# 09_MT7688AN_Peripheral.net
KiCad netlist of a schematic drawn in Altium Designer
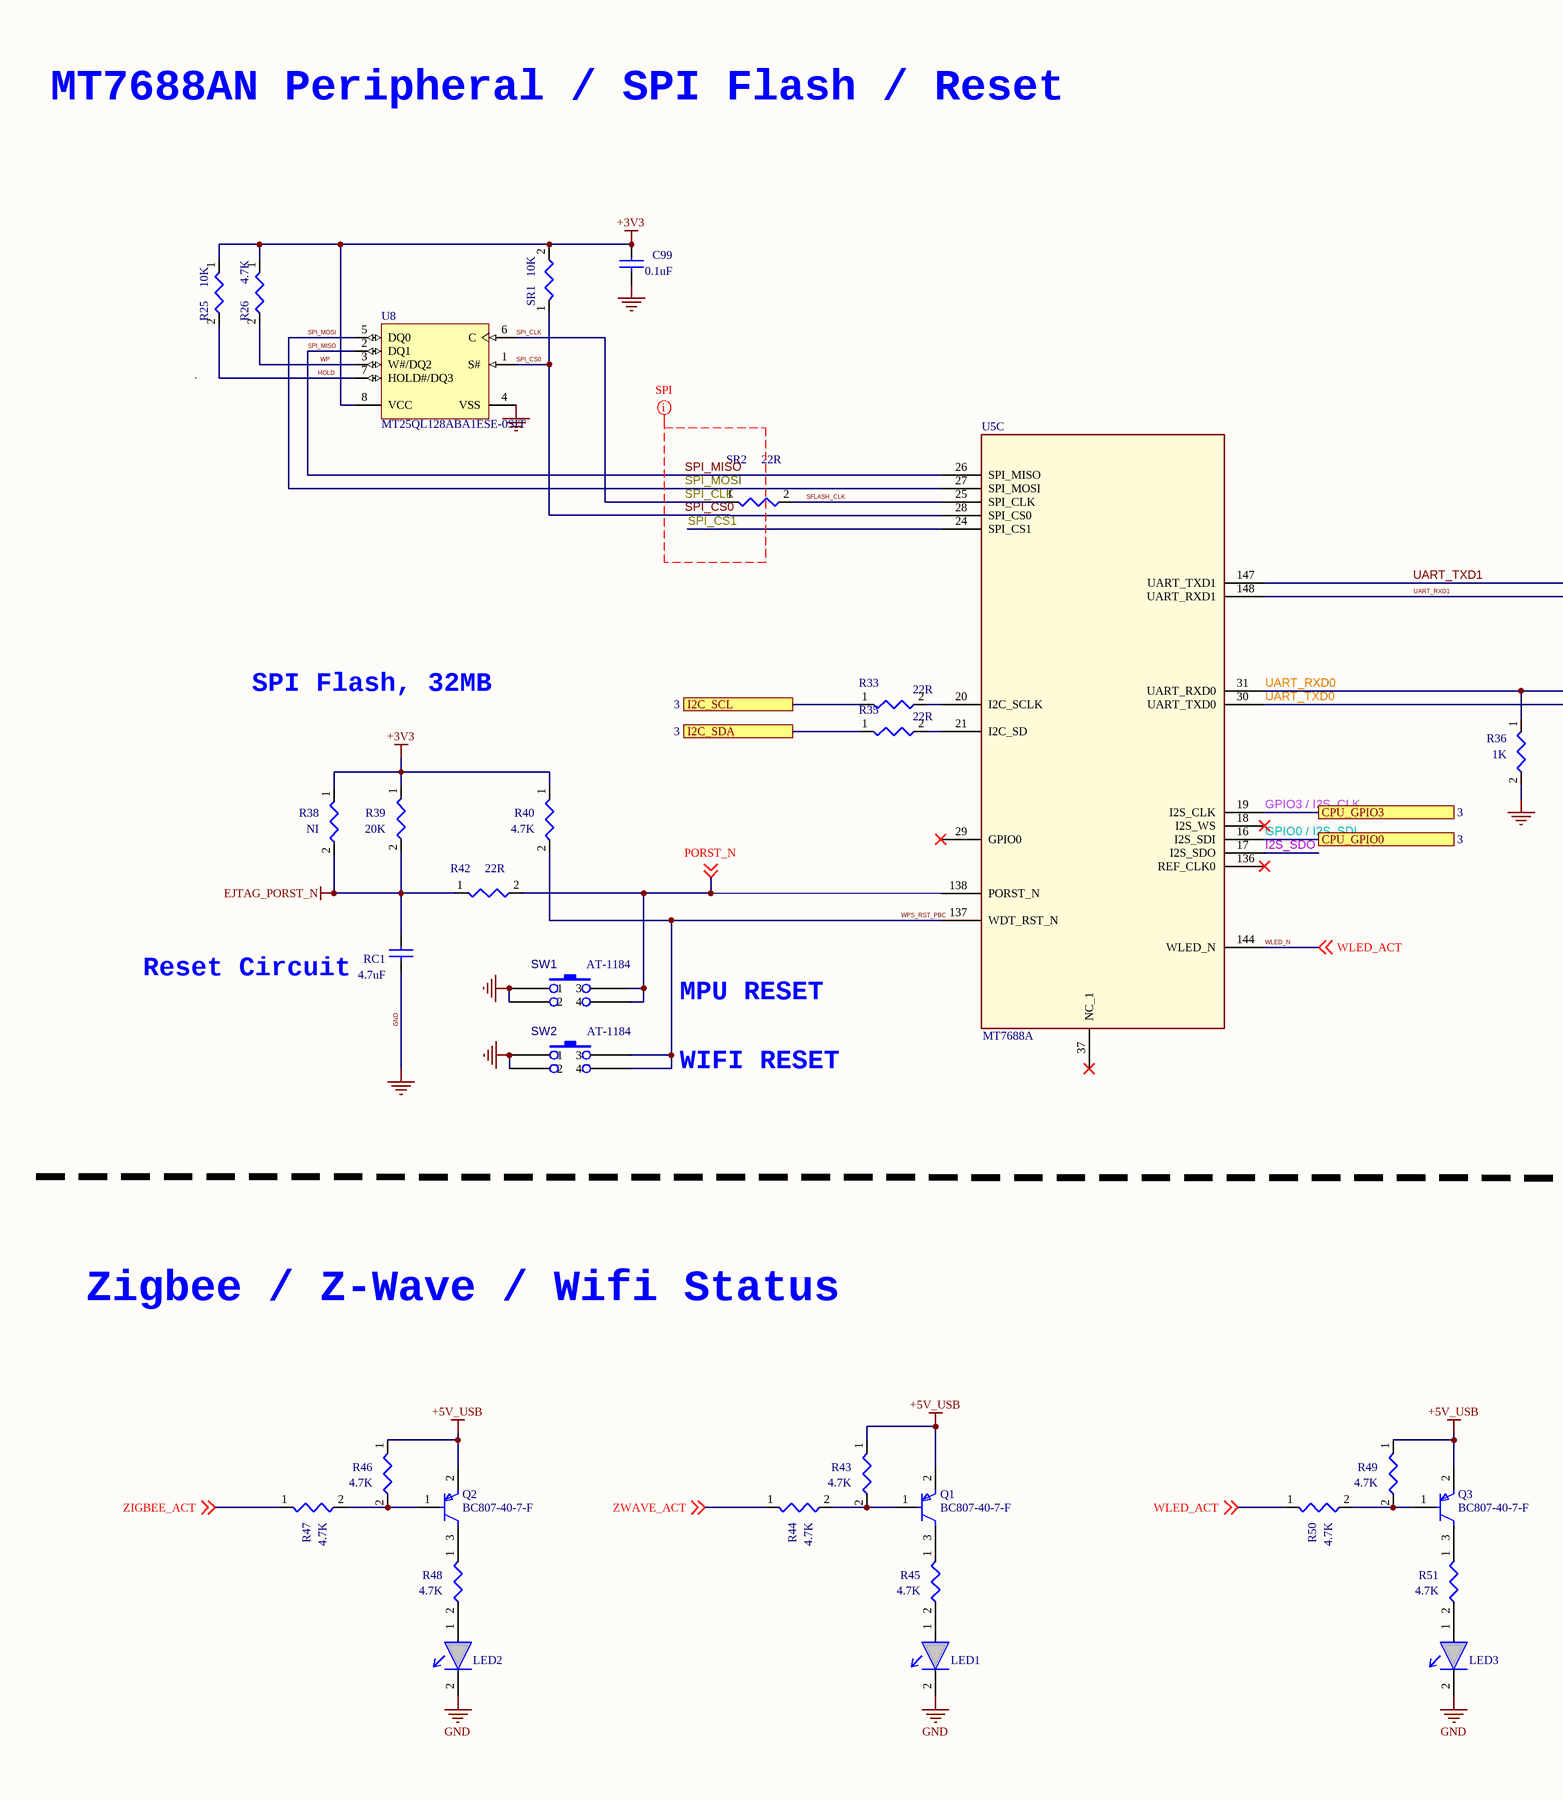
[diagram p0: 09. MT7688AN Peripheral.SchDoc, left]
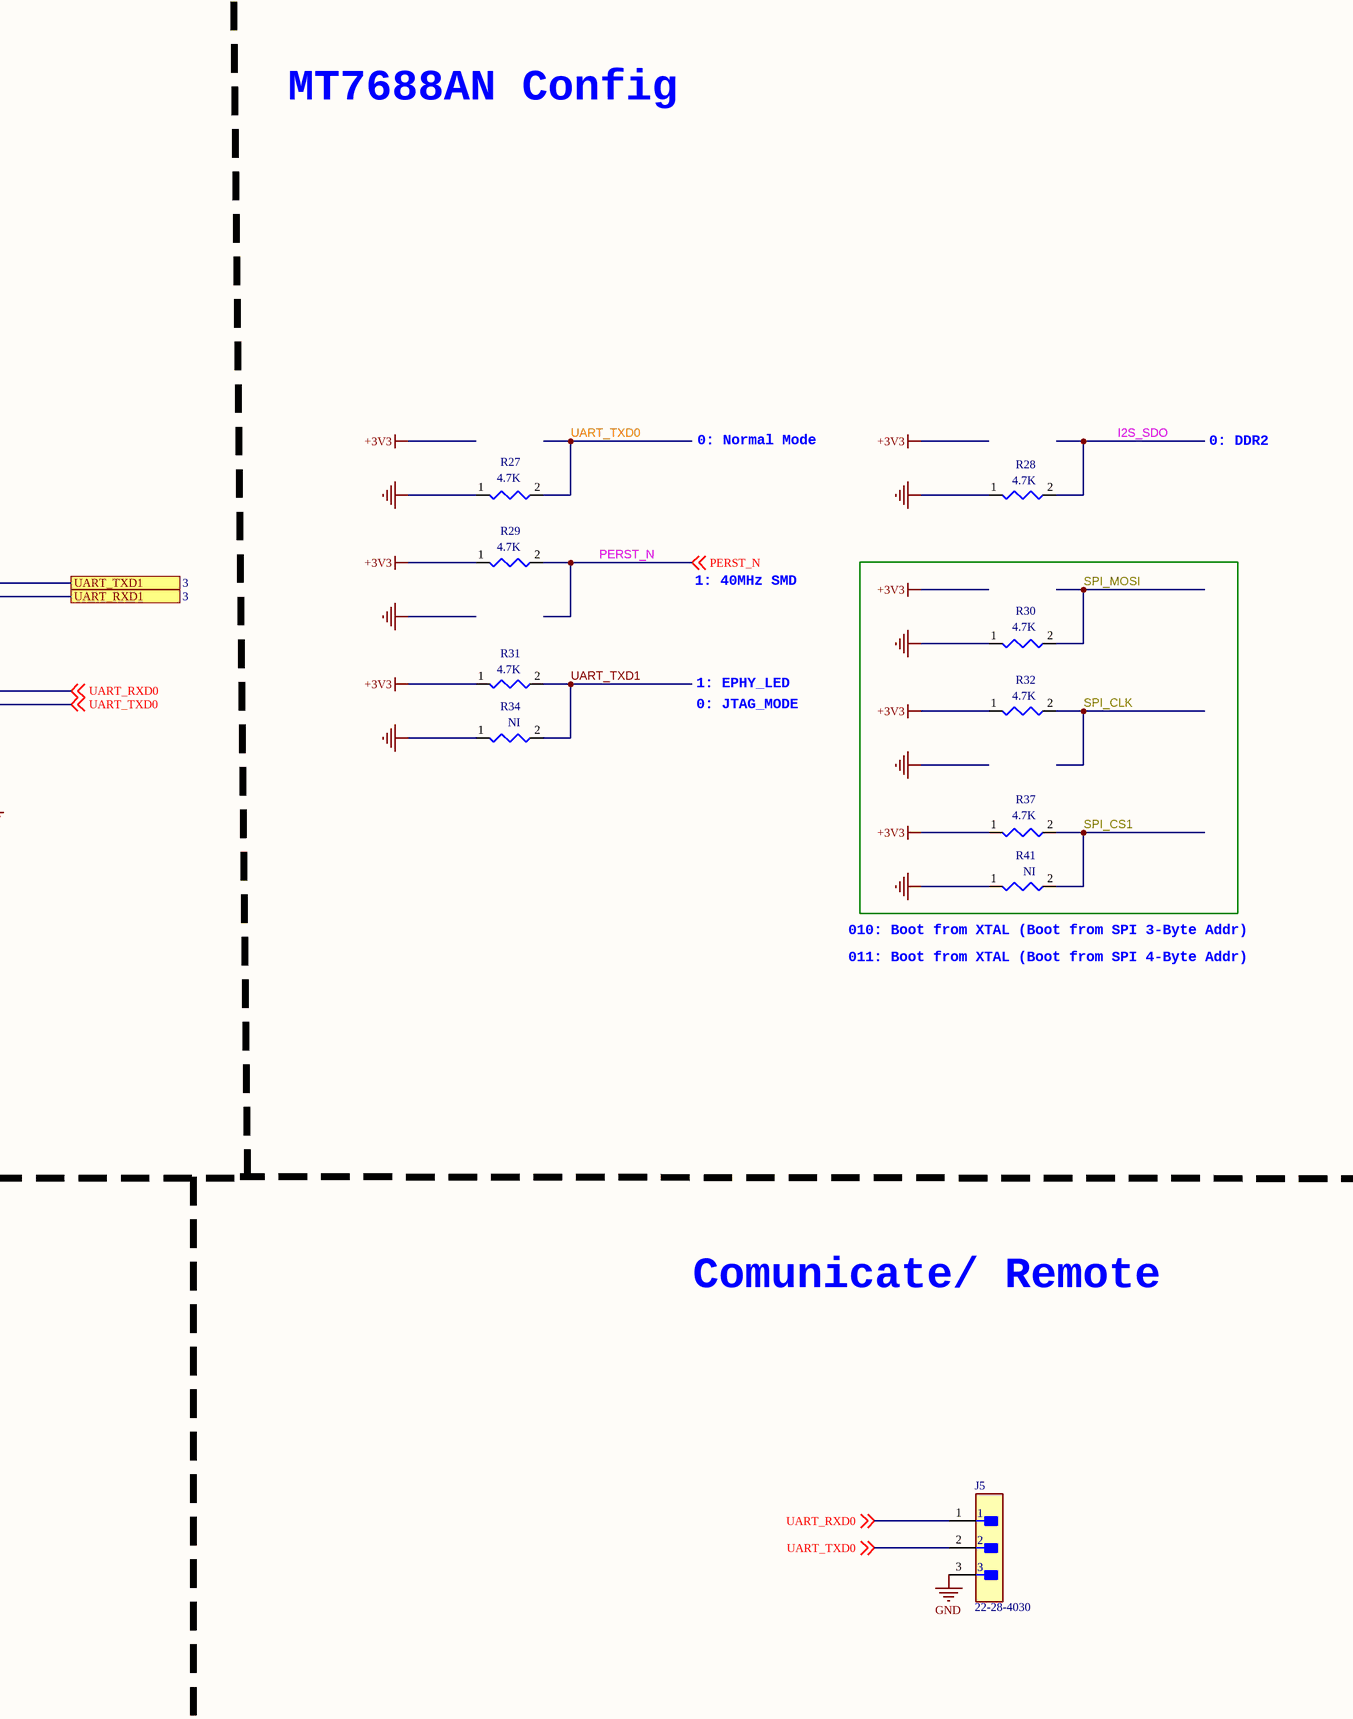
[diagram p1: 09. MT7688AN Peripheral.SchDoc, right]

(export (version "E")
  (design (tool "Eeschema 10.0.6"))
  (components
    (comp (ref "C99")
      (value "0.1uF")
      (footprint "CAPC1005X60X30NL05T10")
      (libsource (lib "MT7688AN") (part "CAP NP"))
    )
    (comp (ref "J5")
      (value "22-28-4030")
      (footprint "FP-22-28-4030-MFG")
      (description "CONN HEADER VERT 3POS 2.54MM")
      (fields
        (field (name "OCTOPART") "https://octopart.com/0022284030-molex-10476094")
        (field (name "MANUFACTURER") "Molex")
      )
      (libsource (lib "Altium Content Vault") (part "0d3f023dd272f625e17a2be33dea85f"))
    )
    (comp (ref "LED1")
      (value "LED 2P")
      (footprint "LED3MM 2P")
      (libsource (lib "SyTungNguyen") (part "LED 2P"))
    )
    (comp (ref "LED2")
      (value "LED 2P")
      (footprint "LED3MM 2P")
      (libsource (lib "SyTungNguyen") (part "LED 2P"))
    )
    (comp (ref "LED3")
      (value "LED 2P")
      (footprint "LED3MM 2P")
      (libsource (lib "SyTungNguyen") (part "LED 2P"))
    )
    (comp (ref "Q1")
      (value "BC807-40-7-F")
      (footprint "FP-SOT23-MFG")
      (description "TRANS PNP 45V 0.5A SOT23")
      (fields
        (field (name "OCTOPART") "https://octopart.com/bc807-40-7-f-diodes+inc.-354302")
        (field (name "MANUFACTURER") "DIODES INC.")
      )
      (libsource (lib "Altium Content Vault") (part "0e8486ed3b47d9c69b8404ba87cf0f7"))
    )
    (comp (ref "Q2")
      (value "BC807-40-7-F")
      (footprint "FP-SOT23-MFG")
      (description "TRANS PNP 45V 0.5A SOT23")
      (fields
        (field (name "OCTOPART") "https://octopart.com/bc807-40-7-f-diodes+inc.-354302")
        (field (name "MANUFACTURER") "DIODES INC.")
      )
      (libsource (lib "Altium Content Vault") (part "0e8486ed3b47d9c69b8404ba87cf0f7"))
    )
    (comp (ref "Q3")
      (value "BC807-40-7-F")
      (footprint "FP-SOT23-MFG")
      (description "TRANS PNP 45V 0.5A SOT23")
      (fields
        (field (name "OCTOPART") "https://octopart.com/bc807-40-7-f-diodes+inc.-354302")
        (field (name "MANUFACTURER") "DIODES INC.")
      )
      (libsource (lib "Altium Content Vault") (part "0e8486ed3b47d9c69b8404ba87cf0f7"))
    )
    (comp (ref "R25")
      (value "10K")
      (footprint "RESC1005X35X25NL10T10")
      (libsource (lib "MT7688AN") (part "RES/0402_3"))
    )
    (comp (ref "R26")
      (value "4.7K")
      (footprint "RESC1005X35X25NL10T10")
      (libsource (lib "MT7688AN") (part "RES/0402_3"))
    )
    (comp (ref "R27")
      (value "4.7K")
      (footprint "RESC1005X35X25NL10T10")
      (libsource (lib "MT7688AN") (part "RES/0402_3"))
    )
    (comp (ref "R28")
      (value "4.7K")
      (footprint "RESC1005X35X25NL10T10")
      (libsource (lib "MT7688AN") (part "RES/0402_3"))
    )
    (comp (ref "R29")
      (value "4.7K")
      (footprint "RESC1005X35X25NL10T10")
      (libsource (lib "MT7688AN") (part "RES/0402_3"))
    )
    (comp (ref "R30")
      (value "4.7K")
      (footprint "RESC1005X35X25NL10T10")
      (libsource (lib "MT7688AN") (part "RES/0402_3"))
    )
    (comp (ref "R31")
      (value "4.7K")
      (footprint "RESC1005X35X25NL10T10")
      (libsource (lib "MT7688AN") (part "RES/0402_3"))
    )
    (comp (ref "R32")
      (value "4.7K")
      (footprint "RESC1005X35X25NL10T10")
      (libsource (lib "MT7688AN") (part "RES/0402_3"))
    )
    (comp (ref "R33")
      (value "22R")
      (footprint "RESC1005X35X25NL10T10")
      (libsource (lib "MT7688AN") (part "RES/0402_3"))
    )
    (comp (ref "R34")
      (value "NI")
      (footprint "RESC1005X35X25NL10T10")
      (libsource (lib "MT7688AN") (part "RES/0402_3"))
    )
    (comp (ref "R35")
      (value "22R")
      (footprint "RESC1005X35X25NL10T10")
      (libsource (lib "MT7688AN") (part "RES/0402_3"))
    )
    (comp (ref "R36")
      (value "1K")
      (footprint "RESC1005X35X25NL10T10")
      (libsource (lib "MT7688AN") (part "RES/0402_3"))
    )
    (comp (ref "R37")
      (value "4.7K")
      (footprint "RESC1005X35X25NL10T10")
      (libsource (lib "MT7688AN") (part "RES/0402_3"))
    )
    (comp (ref "R38")
      (value "NI")
      (footprint "RESC1005X35X25NL10T10")
      (libsource (lib "MT7688AN") (part "RES/0402_3"))
    )
    (comp (ref "R39")
      (value "20K")
      (footprint "RESC1005X35X25NL10T10")
      (libsource (lib "MT7688AN") (part "RES/0402_3"))
    )
    (comp (ref "R40")
      (value "4.7K")
      (footprint "RESC1005X35X25NL10T10")
      (libsource (lib "MT7688AN") (part "RES/0402_3"))
    )
    (comp (ref "R41")
      (value "NI")
      (footprint "RESC1005X35X25NL10T10")
      (libsource (lib "MT7688AN") (part "RES/0402_3"))
    )
    (comp (ref "R42")
      (value "22R")
      (footprint "RESC1005X35X25NL10T10")
      (libsource (lib "MT7688AN") (part "RES/0402_3"))
    )
    (comp (ref "R43")
      (value "4.7K")
      (footprint "RESC1005X35X25NL10T10")
      (libsource (lib "MT7688AN") (part "RES/0402_3"))
    )
    (comp (ref "R44")
      (value "4.7K")
      (footprint "RESC1005X35X25NL10T10")
      (libsource (lib "MT7688AN") (part "RES/0402_3"))
    )
    (comp (ref "R45")
      (value "4.7K")
      (footprint "RESC1609X50X30NL10T20")
      (libsource (lib "MT7688AN") (part "RES/0402_3"))
    )
    (comp (ref "R46")
      (value "4.7K")
      (footprint "RESC1005X35X25NL10T10")
      (libsource (lib "MT7688AN") (part "RES/0402_3"))
    )
    (comp (ref "R47")
      (value "4.7K")
      (footprint "RESC1005X35X25NL10T10")
      (libsource (lib "MT7688AN") (part "RES/0402_3"))
    )
    (comp (ref "R48")
      (value "4.7K")
      (footprint "RESC1609X50X30NL10T20")
      (libsource (lib "MT7688AN") (part "RES/0402_3"))
    )
    (comp (ref "R49")
      (value "4.7K")
      (footprint "RESC1005X35X25NL10T10")
      (libsource (lib "MT7688AN") (part "RES/0402_3"))
    )
    (comp (ref "R50")
      (value "4.7K")
      (footprint "RESC1005X35X25NL10T10")
      (libsource (lib "MT7688AN") (part "RES/0402_3"))
    )
    (comp (ref "R51")
      (value "4.7K")
      (footprint "RESC1609X50X30NL10T20")
      (libsource (lib "MT7688AN") (part "RES/0402_3"))
    )
    (comp (ref "RC1")
      (value "4.7uF")
      (footprint "CAPC1005X60X30NL05T10")
      (libsource (lib "MT7688AN") (part "CAP NP"))
    )
    (comp (ref "SR1")
      (value "10K")
      (footprint "RESC1005X35X25NL10T10")
      (libsource (lib "MT7688AN") (part "RES/0402_3"))
    )
    (comp (ref "SR2")
      (value "22R")
      (footprint "RESC1005X35X25NL10T10")
      (libsource (lib "MT7688AN") (part "RES/0402_3"))
    )
    (comp (ref "SW1")
      (value "AT-1184")
      (footprint "AT-1184 SW")
      (description "TACT Switch, H=1.5mm")
      (fields (field (name "MANUFACTURER") "Panasonic - ECG"))
      (libsource (lib "MT7688AN") (part "SW"))
    )
    (comp (ref "SW2")
      (value "AT-1184")
      (footprint "AT-1184 SW")
      (description "TACT Switch, H=1.5mm")
      (fields (field (name "MANUFACTURER") "Panasonic - ECG"))
      (libsource (lib "MT7688AN") (part "SW"))
    )
    (comp (ref "U5")
      (value "MT7688A")
      (footprint "MT7628AN$2F$DRQFN156$2F$SMD$2F$P0.5$2F$12X12")
      (libsource (lib "MT7688AN") (part "MT7620N-n_26"))
    )
    (comp (ref "U8")
      (value "MT25QL128ABA1ESE-0SIT")
      (footprint "SOIC8_N")
      (fields (field (name "MANUFACTURER") "Micron"))
      (libsource (lib "HAGateWay202205V10") (part "MICT-MT25QL128ABA-SOP2-8"))
    )
  )
  (nets
    (net (code "1") (name "+3V3") (class "Default")
      (node (ref "C99") (pin "1") (pinfunction "1_1") (pintype "passive"))
      (node (ref "R25") (pin "1") (pinfunction "1_1") (pintype "passive"))
      (node (ref "R26") (pin "1") (pinfunction "1_1") (pintype "passive"))
      (node (ref "R29") (pin "1") (pinfunction "1_1") (pintype "passive"))
      (node (ref "R31") (pin "1") (pinfunction "1_1") (pintype "passive"))
      (node (ref "R32") (pin "1") (pinfunction "1_1") (pintype "passive"))
      (node (ref "R37") (pin "1") (pinfunction "1_1") (pintype "passive"))
      (node (ref "R38") (pin "1") (pinfunction "1_1") (pintype "passive"))
      (node (ref "R39") (pin "1") (pinfunction "1_1") (pintype "passive"))
      (node (ref "R40") (pin "1") (pinfunction "1_1") (pintype "passive"))
      (node (ref "SR1") (pin "2") (pinfunction "2_2") (pintype "passive"))
      (node (ref "U8") (pin "8") (pinfunction "VCC_8") (pintype "power_in"))
    )
    (net (code "2") (name "+5V_USB") (class "Default")
      (node (ref "Q1") (pin "2") (pinfunction "E_2") (pintype "passive"))
      (node (ref "Q2") (pin "2") (pinfunction "E_2") (pintype "passive"))
      (node (ref "Q3") (pin "2") (pinfunction "E_2") (pintype "passive"))
      (node (ref "R43") (pin "1") (pinfunction "1_1") (pintype "passive"))
      (node (ref "R46") (pin "1") (pinfunction "1_1") (pintype "passive"))
      (node (ref "R49") (pin "1") (pinfunction "1_1") (pintype "passive"))
    )
    (net (code "3") (name "/GPIO0 {slash} I2S_SDI") (class "Default")
      (node (ref "U5") (pin "16") (pinfunction "I2S_SDI_16") (pintype "passive"))
    )
    (net (code "4") (name "/GPIO3 {slash} I2S_CLK") (class "Default")
      (node (ref "U5") (pin "19") (pinfunction "I2S_CLK_19") (pintype "passive"))
    )
    (net (code "5") (name "/HOLD") (class "Default")
      (node (ref "R25") (pin "2") (pinfunction "2_2") (pintype "passive"))
      (node (ref "U8") (pin "7") (pinfunction "HOLD#/DQ3_7") (pintype "bidirectional"))
    )
    (net (code "6") (name "/I2C_SCL") (class "Default")
      (node (ref "R33") (pin "1") (pinfunction "1_1") (pintype "passive"))
    )
    (net (code "7") (name "/I2C_SDA") (class "Default")
      (node (ref "R35") (pin "1") (pinfunction "1_1") (pintype "passive"))
    )
    (net (code "8") (name "/I2S_SDO") (class "Default")
      (node (ref "R28") (pin "2") (pinfunction "2_2") (pintype "passive"))
      (node (ref "U5") (pin "17") (pinfunction "I2S_SDO_17") (pintype "passive"))
    )
    (net (code "9") (name "/SFLASH_CLK") (class "Default")
      (node (ref "SR2") (pin "2") (pinfunction "2_2") (pintype "passive"))
      (node (ref "U5") (pin "25") (pinfunction "SPI_CLK_25") (pintype "passive"))
    )
    (net (code "10") (name "/SPI_CLK") (class "Default")
      (node (ref "R32") (pin "2") (pinfunction "2_2") (pintype "passive"))
      (node (ref "SR2") (pin "1") (pinfunction "1_1") (pintype "passive"))
      (node (ref "U8") (pin "6") (pinfunction "C_6") (pintype "input"))
    )
    (net (code "11") (name "/SPI_CS0") (class "Default")
      (node (ref "SR1") (pin "1") (pinfunction "1_1") (pintype "passive"))
      (node (ref "U5") (pin "28") (pinfunction "SPI_CS0_28") (pintype "passive"))
      (node (ref "U8") (pin "1") (pinfunction "S#_1") (pintype "input"))
    )
    (net (code "12") (name "/SPI_CS1") (class "Default")
      (node (ref "R37") (pin "2") (pinfunction "2_2") (pintype "passive"))
      (node (ref "R41") (pin "2") (pinfunction "2_2") (pintype "passive"))
      (node (ref "U5") (pin "24") (pinfunction "SPI_CS1_24") (pintype "passive"))
    )
    (net (code "13") (name "/SPI_MISO") (class "Default")
      (node (ref "U5") (pin "26") (pinfunction "SPI_MISO_26") (pintype "passive"))
      (node (ref "U8") (pin "2") (pinfunction "DQ1_2") (pintype "bidirectional"))
    )
    (net (code "14") (name "/SPI_MOSI") (class "Default")
      (node (ref "R30") (pin "2") (pinfunction "2_2") (pintype "passive"))
      (node (ref "U5") (pin "27") (pinfunction "SPI_MOSI_27") (pintype "passive"))
      (node (ref "U8") (pin "5") (pinfunction "DQ0_5") (pintype "bidirectional"))
    )
    (net (code "15") (name "/UART_RXD1") (class "Default")
      (node (ref "U5") (pin "148") (pinfunction "UART_RXD1_148") (pintype "passive"))
    )
    (net (code "16") (name "/UART_TXD1") (class "Default")
      (node (ref "R31") (pin "2") (pinfunction "2_2") (pintype "passive"))
      (node (ref "R34") (pin "2") (pinfunction "2_2") (pintype "passive"))
      (node (ref "U5") (pin "147") (pinfunction "UART_TXD1_147") (pintype "passive"))
    )
    (net (code "17") (name "/WP") (class "Default")
      (node (ref "R26") (pin "2") (pinfunction "2_2") (pintype "passive"))
      (node (ref "U8") (pin "3") (pinfunction "W#/DQ2_3") (pintype "bidirectional"))
    )
    (net (code "18") (name "/WPS_RST_PBC") (class "Default")
      (node (ref "R40") (pin "2") (pinfunction "2_2") (pintype "passive"))
      (node (ref "SW2") (pin "3") (pinfunction "3_3") (pintype "passive"))
      (node (ref "SW2") (pin "4") (pinfunction "4_4") (pintype "passive"))
      (node (ref "U5") (pin "137") (pinfunction "WDT_RST_N_137") (pintype "passive"))
    )
    (net (code "19") (name "EJTAG_PORST_N") (class "Default")
      (node (ref "R38") (pin "2") (pinfunction "2_2") (pintype "passive"))
      (node (ref "R39") (pin "2") (pinfunction "2_2") (pintype "passive"))
      (node (ref "R42") (pin "1") (pinfunction "1_1") (pintype "passive"))
      (node (ref "RC1") (pin "1") (pinfunction "1_1") (pintype "passive"))
    )
    (net (code "20") (name "GND") (class "Default")
      (node (ref "C99") (pin "2") (pinfunction "2_2") (pintype "passive"))
      (node (ref "J5") (pin "3") (pinfunction "3_3") (pintype "passive"))
      (node (ref "LED1") (pin "2") (pinfunction "2_2") (pintype "passive"))
      (node (ref "LED2") (pin "2") (pinfunction "2_2") (pintype "passive"))
      (node (ref "LED3") (pin "2") (pinfunction "2_2") (pintype "passive"))
      (node (ref "R27") (pin "1") (pinfunction "1_1") (pintype "passive"))
      (node (ref "R28") (pin "1") (pinfunction "1_1") (pintype "passive"))
      (node (ref "R30") (pin "1") (pinfunction "1_1") (pintype "passive"))
      (node (ref "R34") (pin "1") (pinfunction "1_1") (pintype "passive"))
      (node (ref "R36") (pin "2") (pinfunction "2_2") (pintype "passive"))
      (node (ref "R41") (pin "1") (pinfunction "1_1") (pintype "passive"))
      (node (ref "RC1") (pin "2") (pinfunction "2_2") (pintype "passive"))
      (node (ref "SW1") (pin "1") (pinfunction "1_1") (pintype "passive"))
      (node (ref "SW1") (pin "2") (pinfunction "2_2") (pintype "passive"))
      (node (ref "SW2") (pin "1") (pinfunction "1_1") (pintype "passive"))
      (node (ref "SW2") (pin "2") (pinfunction "2_2") (pintype "passive"))
      (node (ref "U8") (pin "4") (pinfunction "VSS_4") (pintype "power_in"))
    )
    (net (code "21") (name "Net-(LED1-Pad1)") (class "Default")
      (node (ref "LED1") (pin "1") (pinfunction "1_1") (pintype "passive"))
      (node (ref "R45") (pin "2") (pinfunction "2_2") (pintype "passive"))
    )
    (net (code "22") (name "Net-(LED2-Pad1)") (class "Default")
      (node (ref "LED2") (pin "1") (pinfunction "1_1") (pintype "passive"))
      (node (ref "R48") (pin "2") (pinfunction "2_2") (pintype "passive"))
    )
    (net (code "23") (name "Net-(LED3-Pad1)") (class "Default")
      (node (ref "LED3") (pin "1") (pinfunction "1_1") (pintype "passive"))
      (node (ref "R51") (pin "2") (pinfunction "2_2") (pintype "passive"))
    )
    (net (code "24") (name "Net-(Q1-B)") (class "Default")
      (node (ref "Q1") (pin "1") (pinfunction "B_1") (pintype "passive"))
      (node (ref "R43") (pin "2") (pinfunction "2_2") (pintype "passive"))
      (node (ref "R44") (pin "2") (pinfunction "2_2") (pintype "passive"))
    )
    (net (code "25") (name "Net-(Q1-C)") (class "Default")
      (node (ref "Q1") (pin "3") (pinfunction "C_3") (pintype "passive"))
      (node (ref "R45") (pin "1") (pinfunction "1_1") (pintype "passive"))
    )
    (net (code "26") (name "Net-(Q2-B)") (class "Default")
      (node (ref "Q2") (pin "1") (pinfunction "B_1") (pintype "passive"))
      (node (ref "R46") (pin "2") (pinfunction "2_2") (pintype "passive"))
      (node (ref "R47") (pin "2") (pinfunction "2_2") (pintype "passive"))
    )
    (net (code "27") (name "Net-(Q2-C)") (class "Default")
      (node (ref "Q2") (pin "3") (pinfunction "C_3") (pintype "passive"))
      (node (ref "R48") (pin "1") (pinfunction "1_1") (pintype "passive"))
    )
    (net (code "28") (name "Net-(Q3-B)") (class "Default")
      (node (ref "Q3") (pin "1") (pinfunction "B_1") (pintype "passive"))
      (node (ref "R49") (pin "2") (pinfunction "2_2") (pintype "passive"))
      (node (ref "R50") (pin "2") (pinfunction "2_2") (pintype "passive"))
    )
    (net (code "29") (name "Net-(Q3-C)") (class "Default")
      (node (ref "Q3") (pin "3") (pinfunction "C_3") (pintype "passive"))
      (node (ref "R51") (pin "1") (pinfunction "1_1") (pintype "passive"))
    )
    (net (code "30") (name "Net-(U5C-I2C_SCLK)") (class "Default")
      (node (ref "R33") (pin "2") (pinfunction "2_2") (pintype "passive"))
      (node (ref "U5") (pin "20") (pinfunction "I2C_SCLK_20") (pintype "passive"))
    )
    (net (code "31") (name "Net-(U5C-I2C_SD)") (class "Default")
      (node (ref "R35") (pin "2") (pinfunction "2_2") (pintype "passive"))
      (node (ref "U5") (pin "21") (pinfunction "I2C_SD_21") (pintype "passive"))
    )
    (net (code "32") (name "PERST_N") (class "Default")
      (node (ref "R29") (pin "2") (pinfunction "2_2") (pintype "passive"))
    )
    (net (code "33") (name "PORST_N") (class "Default")
      (node (ref "R42") (pin "2") (pinfunction "2_2") (pintype "passive"))
      (node (ref "SW1") (pin "3") (pinfunction "3_3") (pintype "passive"))
      (node (ref "SW1") (pin "4") (pinfunction "4_4") (pintype "passive"))
      (node (ref "U5") (pin "138") (pinfunction "PORST_N_138") (pintype "passive"))
    )
    (net (code "34") (name "UART_RXD0") (class "Default")
      (node (ref "J5") (pin "1") (pinfunction "1_1") (pintype "passive"))
      (node (ref "R36") (pin "1") (pinfunction "1_1") (pintype "passive"))
      (node (ref "U5") (pin "31") (pinfunction "UART_RXD0_31") (pintype "passive"))
    )
    (net (code "35") (name "UART_TXD0") (class "Default")
      (node (ref "J5") (pin "2") (pinfunction "2_2") (pintype "passive"))
      (node (ref "R27") (pin "2") (pinfunction "2_2") (pintype "passive"))
      (node (ref "U5") (pin "30") (pinfunction "UART_TXD0_30") (pintype "passive"))
    )
    (net (code "36") (name "WLED_ACT") (class "Default")
      (node (ref "R50") (pin "1") (pinfunction "1_1") (pintype "passive"))
      (node (ref "U5") (pin "144") (pinfunction "WLED_N_144") (pintype "passive"))
    )
    (net (code "37") (name "ZIGBEE_ACT") (class "Default")
      (node (ref "R47") (pin "1") (pinfunction "1_1") (pintype "passive"))
    )
    (net (code "38") (name "ZWAVE_ACT") (class "Default")
      (node (ref "R44") (pin "1") (pinfunction "1_1") (pintype "passive"))
    )
    (net (code "39") (name "unconnected-(U5C-GPIO0-Pad29)") (class "Default")
      (node (ref "U5") (pin "29") (pinfunction "GPIO0_29") (pintype "passive+no_connect"))
    )
    (net (code "40") (name "unconnected-(U5C-I2S_WS-Pad18)") (class "Default")
      (node (ref "U5") (pin "18") (pinfunction "I2S_WS_18") (pintype "passive+no_connect"))
    )
    (net (code "41") (name "unconnected-(U5C-NC_1-Pad37)") (class "Default")
      (node (ref "U5") (pin "37") (pinfunction "NC_1_37") (pintype "passive+no_connect"))
    )
    (net (code "42") (name "unconnected-(U5C-REF_CLK0-Pad136)") (class "Default")
      (node (ref "U5") (pin "136") (pinfunction "REF_CLK0_136") (pintype "passive+no_connect"))
    )
  )
)
